# untitled.net
KiCad netlist of a schematic drawn in EAGLE
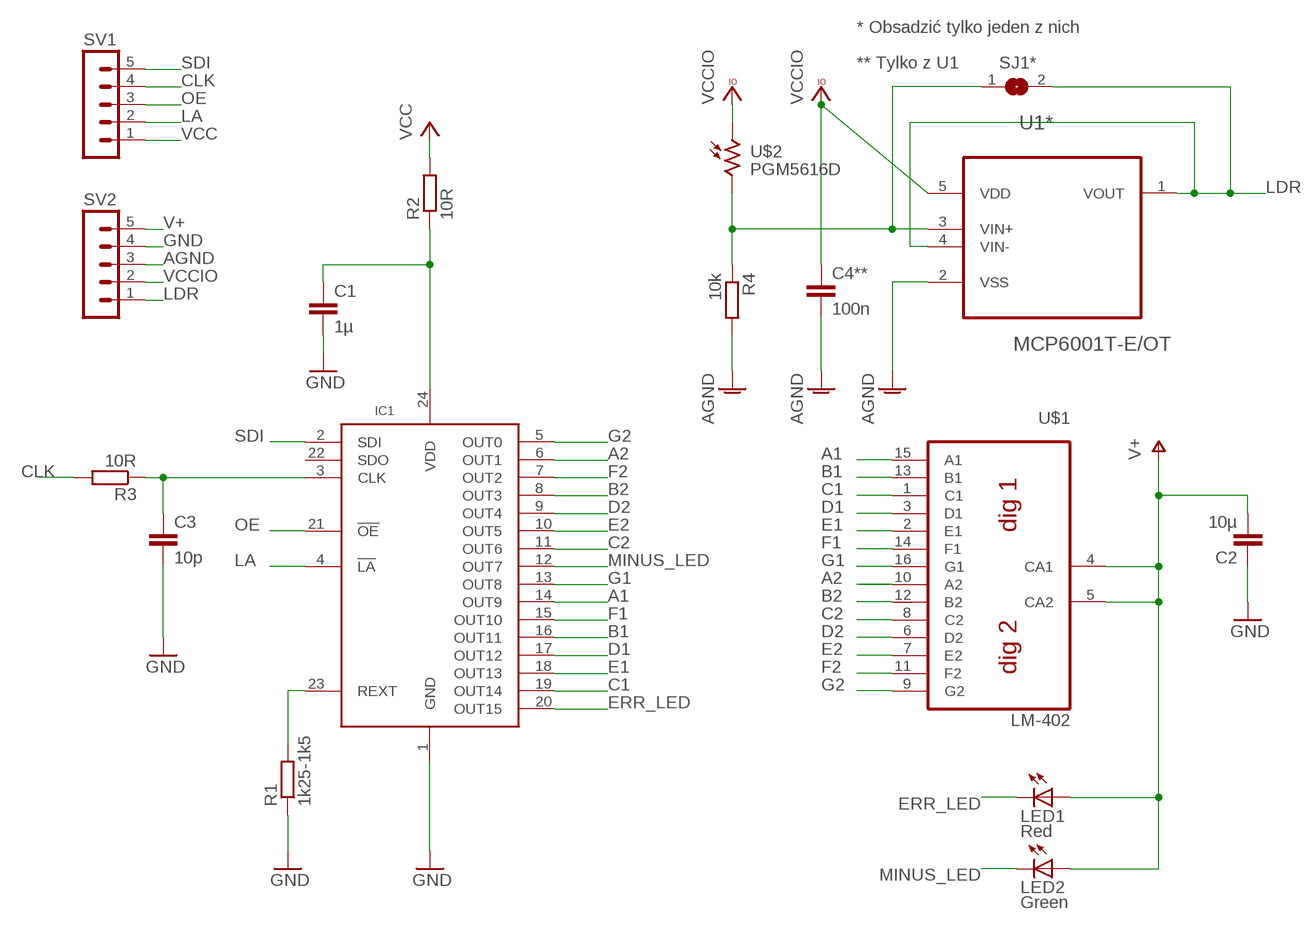
[diagram p0: schematic, sheet 1]

(export (version "E")
  (design (tool "Eeschema 10.0.6"))
  (components
    (comp (ref "C1")
      (value "1µ")
      (footprint "eagle-import:C0603K")
      (libsource (lib "eagle-import") (part "C-EUC0603K"))
    )
    (comp (ref "C2")
      (value "10µ")
      (footprint "eagle-import:C0603K")
      (libsource (lib "eagle-import") (part "C-EUC0603K"))
    )
    (comp (ref "C3")
      (value "10p")
      (footprint "eagle-import:C050-030X075")
      (libsource (lib "eagle-import") (part "C-EU050-030X075"))
    )
    (comp (ref "C4**")
      (value "100n")
      (footprint "eagle-import:C0603K")
      (libsource (lib "eagle-import") (part "C-EUC0603K"))
    )
    (comp (ref "IC1")
      (value "SCT24")
      (footprint "eagle-import:SSOP24")
      (libsource (lib "eagle-import") (part "SCT24"))
    )
    (comp (ref "LED1")
      (value "Red")
      (footprint "eagle-import:LED3MM")
      (libsource (lib "eagle-import") (part "LED3MM"))
    )
    (comp (ref "LED2")
      (value "Green")
      (footprint "eagle-import:LED3MM")
      (libsource (lib "eagle-import") (part "LED3MM"))
    )
    (comp (ref "R1")
      (value "1k25-1k5")
      (footprint "eagle-import:M0805")
      (libsource (lib "eagle-import") (part "R-EU_M0805"))
    )
    (comp (ref "R2")
      (value "10R")
      (footprint "eagle-import:R0805")
      (libsource (lib "eagle-import") (part "R-EU_R0805"))
    )
    (comp (ref "R3")
      (value "10R")
      (footprint "eagle-import:M0805")
      (libsource (lib "eagle-import") (part "R-EU_M0805"))
    )
    (comp (ref "R4")
      (value "10k")
      (footprint "eagle-import:M0805")
      (libsource (lib "eagle-import") (part "R-EU_M0805"))
    )
    (comp (ref "SJ1*")
      (value "SJ")
      (footprint "eagle-import:SJ")
      (libsource (lib "eagle-import") (part "SJ"))
    )
    (comp (ref "SV1")
      (value "MA05-1")
      (footprint "eagle-import:MA05-1")
      (libsource (lib "eagle-import") (part "MA05-1"))
    )
    (comp (ref "SV2")
      (value "MA05-1")
      (footprint "eagle-import:MA05-1")
      (libsource (lib "eagle-import") (part "MA05-1"))
    )
    (comp (ref "U$1")
      (value "LB-402")
      (footprint "eagle-import:LB-402")
      (libsource (lib "eagle-import") (part "LB-402"))
    )
    (comp (ref "U$2")
      (value "PGM5616D")
      (footprint "eagle-import:PHOTO_5_34")
      (libsource (lib "eagle-import") (part "PGM5616D"))
    )
    (comp (ref "U1*")
      (value "MCP6001T-E/OT")
      (footprint "eagle-import:SOT95P270X145-5N")
      (libsource (lib "eagle-import") (part "MCP6001T-E/OT"))
    )
  )
  (nets
    (net (code "1") (name "/A1") (class "Default")
      (node (ref "IC1") (pin "14") (pinfunction "OUT9_14") (pintype "bidirectional"))
      (node (ref "U$1") (pin "15") (pinfunction "A1_15") (pintype "passive"))
    )
    (net (code "2") (name "/A2") (class "Default")
      (node (ref "IC1") (pin "6") (pinfunction "OUT1_6") (pintype "bidirectional"))
      (node (ref "U$1") (pin "10") (pinfunction "A2_10") (pintype "passive"))
    )
    (net (code "3") (name "/B1") (class "Default")
      (node (ref "IC1") (pin "16") (pinfunction "OUT11_16") (pintype "bidirectional"))
      (node (ref "U$1") (pin "13") (pinfunction "B1_13") (pintype "passive"))
    )
    (net (code "4") (name "/B2") (class "Default")
      (node (ref "IC1") (pin "8") (pinfunction "OUT3_8") (pintype "bidirectional"))
      (node (ref "U$1") (pin "12") (pinfunction "B2_12") (pintype "passive"))
    )
    (net (code "5") (name "/C1") (class "Default")
      (node (ref "IC1") (pin "19") (pinfunction "OUT14_19") (pintype "bidirectional"))
      (node (ref "U$1") (pin "1") (pinfunction "C1_1") (pintype "passive"))
    )
    (net (code "6") (name "/C2") (class "Default")
      (node (ref "IC1") (pin "11") (pinfunction "OUT6_11") (pintype "bidirectional"))
      (node (ref "U$1") (pin "8") (pinfunction "C2_8") (pintype "passive"))
    )
    (net (code "7") (name "/CLK") (class "Default")
      (node (ref "R3") (pin "2") (pinfunction "2_2") (pintype "passive"))
      (node (ref "SV1") (pin "4") (pinfunction "4_4") (pintype "passive"))
    )
    (net (code "8") (name "/D1") (class "Default")
      (node (ref "IC1") (pin "17") (pinfunction "OUT12_17") (pintype "bidirectional"))
      (node (ref "U$1") (pin "3") (pinfunction "D1_3") (pintype "passive"))
    )
    (net (code "9") (name "/D2") (class "Default")
      (node (ref "IC1") (pin "9") (pinfunction "OUT4_9") (pintype "bidirectional"))
      (node (ref "U$1") (pin "6") (pinfunction "D2_6") (pintype "passive"))
    )
    (net (code "10") (name "/E1") (class "Default")
      (node (ref "IC1") (pin "18") (pinfunction "OUT13_18") (pintype "bidirectional"))
      (node (ref "U$1") (pin "2") (pinfunction "E1_2") (pintype "passive"))
    )
    (net (code "11") (name "/E2") (class "Default")
      (node (ref "IC1") (pin "10") (pinfunction "OUT5_10") (pintype "bidirectional"))
      (node (ref "U$1") (pin "7") (pinfunction "E2_7") (pintype "passive"))
    )
    (net (code "12") (name "/ERR_LED") (class "Default")
      (node (ref "IC1") (pin "20") (pinfunction "OUT15_20") (pintype "bidirectional"))
      (node (ref "LED1") (pin "K") (pinfunction "C_K") (pintype "passive"))
    )
    (net (code "13") (name "/F1") (class "Default")
      (node (ref "IC1") (pin "15") (pinfunction "OUT10_15") (pintype "bidirectional"))
      (node (ref "U$1") (pin "14") (pinfunction "F1_14") (pintype "passive"))
    )
    (net (code "14") (name "/F2") (class "Default")
      (node (ref "IC1") (pin "7") (pinfunction "OUT2_7") (pintype "bidirectional"))
      (node (ref "U$1") (pin "11") (pinfunction "F2_11") (pintype "passive"))
    )
    (net (code "15") (name "/G1") (class "Default")
      (node (ref "IC1") (pin "13") (pinfunction "OUT8_13") (pintype "bidirectional"))
      (node (ref "U$1") (pin "16") (pinfunction "G1_16") (pintype "passive"))
    )
    (net (code "16") (name "/G2") (class "Default")
      (node (ref "IC1") (pin "5") (pinfunction "OUT0_5") (pintype "bidirectional"))
      (node (ref "U$1") (pin "9") (pinfunction "G2_9") (pintype "passive"))
    )
    (net (code "17") (name "/LA") (class "Default")
      (node (ref "IC1") (pin "4") (pinfunction "~{LA}_4") (pintype "bidirectional"))
      (node (ref "SV1") (pin "2") (pinfunction "2_2") (pintype "passive"))
    )
    (net (code "18") (name "/LDR") (class "Default")
      (node (ref "SJ1*") (pin "2") (pinfunction "2_2") (pintype "passive"))
      (node (ref "SV2") (pin "1") (pinfunction "1_1") (pintype "passive"))
      (node (ref "U1*") (pin "1") (pinfunction "VOUT_1") (pintype "output"))
      (node (ref "U1*") (pin "4") (pinfunction "VIN-_4") (pintype "input"))
    )
    (net (code "19") (name "/MINUS_LED") (class "Default")
      (node (ref "IC1") (pin "12") (pinfunction "OUT7_12") (pintype "bidirectional"))
      (node (ref "LED2") (pin "K") (pinfunction "C_K") (pintype "passive"))
    )
    (net (code "20") (name "/OE") (class "Default")
      (node (ref "IC1") (pin "21") (pinfunction "~{OE}_21") (pintype "bidirectional"))
      (node (ref "SV1") (pin "3") (pinfunction "3_3") (pintype "passive"))
    )
    (net (code "21") (name "/SDI") (class "Default")
      (node (ref "IC1") (pin "2") (pinfunction "SDI_2") (pintype "bidirectional"))
      (node (ref "SV1") (pin "5") (pinfunction "5_5") (pintype "passive"))
    )
    (net (code "22") (name "AGND") (class "Default")
      (node (ref "C4**") (pin "2") (pinfunction "2_2") (pintype "passive"))
      (node (ref "R4") (pin "2") (pinfunction "2_2") (pintype "passive"))
      (node (ref "SV2") (pin "3") (pinfunction "3_3") (pintype "passive"))
      (node (ref "U1*") (pin "2") (pinfunction "VSS_2") (pintype "passive"))
    )
    (net (code "23") (name "GND") (class "Default")
      (node (ref "C1") (pin "2") (pinfunction "2_2") (pintype "passive"))
      (node (ref "C2") (pin "1") (pinfunction "1_1") (pintype "passive"))
      (node (ref "C3") (pin "2") (pinfunction "2_2") (pintype "passive"))
      (node (ref "IC1") (pin "1") (pinfunction "GND_1") (pintype "bidirectional"))
      (node (ref "R1") (pin "1") (pinfunction "1_1") (pintype "passive"))
      (node (ref "SV2") (pin "4") (pinfunction "4_4") (pintype "passive"))
    )
    (net (code "24") (name "Net-(IC1-CLK)") (class "Default")
      (node (ref "C3") (pin "1") (pinfunction "1_1") (pintype "passive"))
      (node (ref "IC1") (pin "3") (pinfunction "CLK_3") (pintype "bidirectional"))
      (node (ref "R3") (pin "1") (pinfunction "1_1") (pintype "passive"))
    )
    (net (code "25") (name "Net-(IC1-REXT)") (class "Default")
      (node (ref "IC1") (pin "23") (pinfunction "REXT_23") (pintype "bidirectional"))
      (node (ref "R1") (pin "2") (pinfunction "2_2") (pintype "passive"))
    )
    (net (code "26") (name "Net-(IC1-VDD)") (class "Default")
      (node (ref "C1") (pin "1") (pinfunction "1_1") (pintype "passive"))
      (node (ref "IC1") (pin "24") (pinfunction "VDD_24") (pintype "bidirectional"))
      (node (ref "R2") (pin "1") (pinfunction "1_1") (pintype "passive"))
    )
    (net (code "27") (name "Net-(U1*-VIN+)") (class "Default")
      (node (ref "R4") (pin "1") (pinfunction "1_1") (pintype "passive"))
      (node (ref "SJ1*") (pin "1") (pinfunction "1_1") (pintype "passive"))
      (node (ref "U$2") (pin "2") (pinfunction "2_2") (pintype "passive"))
      (node (ref "U1*") (pin "3") (pinfunction "VIN+_3") (pintype "input"))
    )
    (net (code "28") (name "V+") (class "Default")
      (node (ref "C2") (pin "2") (pinfunction "2_2") (pintype "passive"))
      (node (ref "LED1") (pin "A") (pinfunction "A_A") (pintype "passive"))
      (node (ref "LED2") (pin "A") (pinfunction "A_A") (pintype "passive"))
      (node (ref "SV2") (pin "5") (pinfunction "5_5") (pintype "passive"))
      (node (ref "U$1") (pin "4") (pinfunction "CA1_4") (pintype "passive"))
      (node (ref "U$1") (pin "5") (pinfunction "CA2_5") (pintype "passive"))
    )
    (net (code "29") (name "VCC") (class "Default")
      (node (ref "R2") (pin "2") (pinfunction "2_2") (pintype "passive"))
      (node (ref "SV1") (pin "1") (pinfunction "1_1") (pintype "passive"))
    )
    (net (code "30") (name "VCCIO") (class "Default")
      (node (ref "C4**") (pin "1") (pinfunction "1_1") (pintype "passive"))
      (node (ref "SV2") (pin "2") (pinfunction "2_2") (pintype "passive"))
      (node (ref "U$2") (pin "1") (pinfunction "1_1") (pintype "passive"))
      (node (ref "U1*") (pin "5") (pinfunction "VDD_5") (pintype "power_in"))
    )
    (net (code "31") (name "unconnected-(IC1-SDO-Pad22)") (class "Default")
      (node (ref "IC1") (pin "22") (pinfunction "SDO_22") (pintype "bidirectional"))
    )
  )
)
